# Interfaces_and_Connectors.net
KiCad netlist of a schematic drawn in Altium Designer
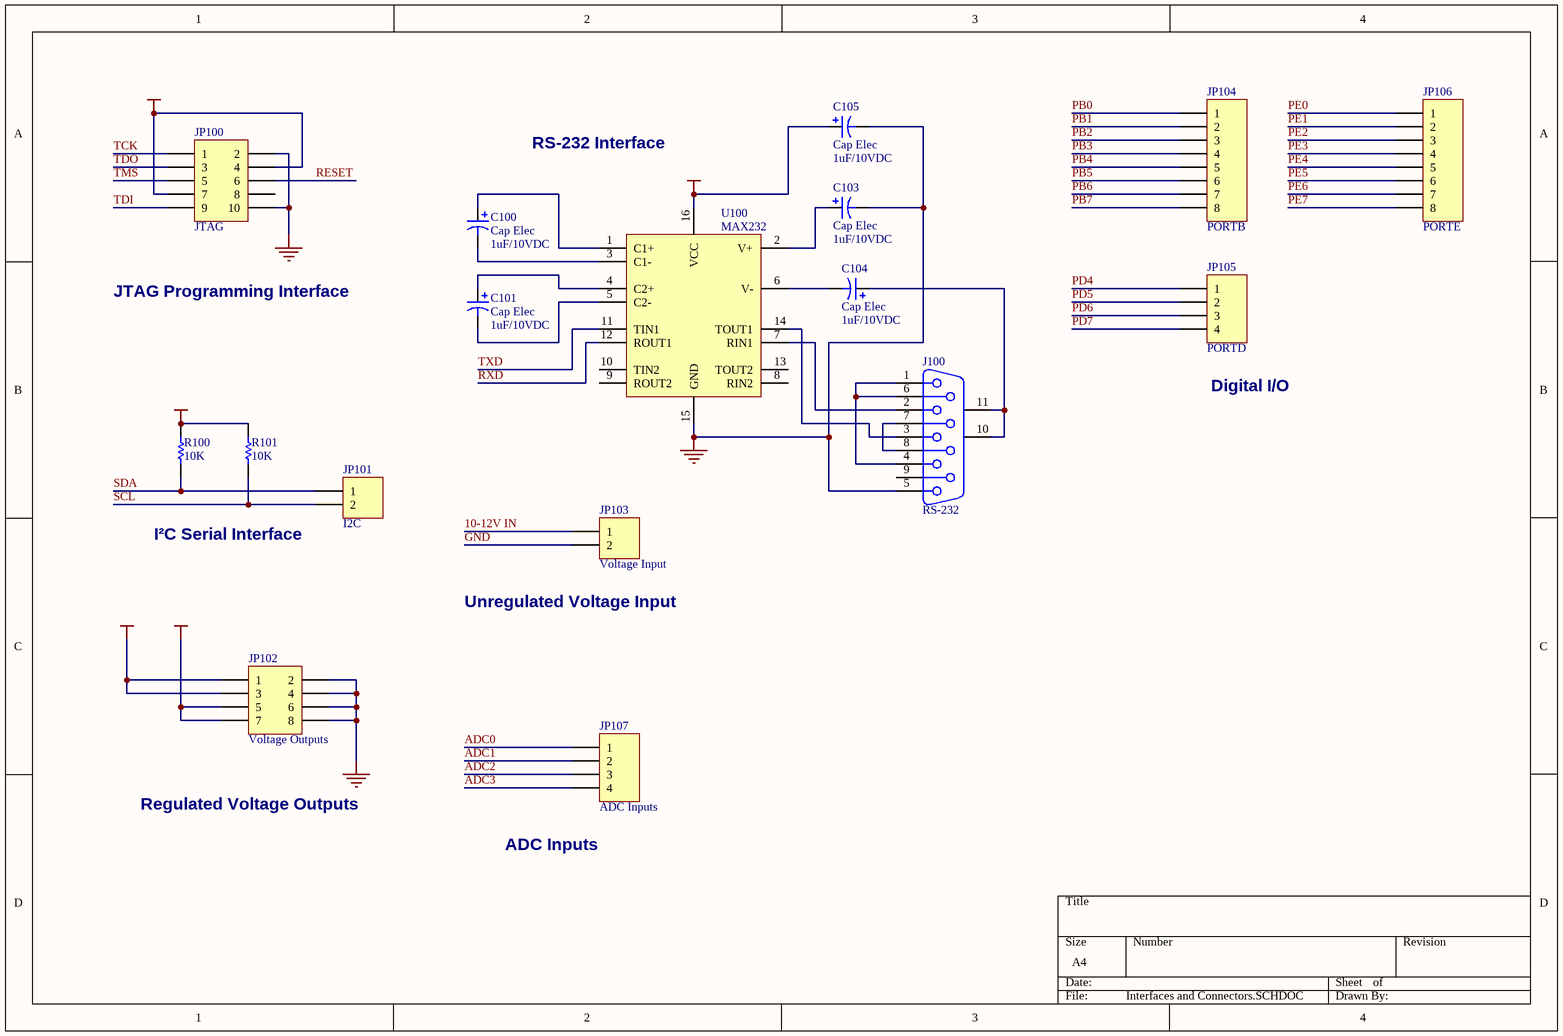
[diagram p0: Interfaces and Connectors.SCHDOC]

(export (version "E")
  (design (tool "Eeschema 10.0.6"))
  (components
    (comp (ref "C100")
      (value "Cap Elec")
      (footprint "CAPR5-4X5")
      (description "Polarized Capacitor (Axial)")
      (fields (field (name "ALTIUM_VALUE") "1uF/10VDC") (field (name "PUBLISHER") "Altium Limited"))
      (libsource (lib "Miscellaneous Devices") (part "Cap Pol2"))
    )
    (comp (ref "C101")
      (value "Cap Elec")
      (footprint "CAPR5-4X5")
      (description "Polarized Capacitor (Axial)")
      (fields (field (name "ALTIUM_VALUE") "1uF/10VDC") (field (name "PUBLISHER") "Altium Limited"))
      (libsource (lib "Miscellaneous Devices") (part "Cap Pol2"))
    )
    (comp (ref "C103")
      (value "Cap Elec")
      (footprint "CAPR5-4X5")
      (description "Polarized Capacitor (Axial)")
      (fields (field (name "ALTIUM_VALUE") "1uF/10VDC") (field (name "PUBLISHER") "Altium Limited"))
      (libsource (lib "Miscellaneous Devices") (part "Cap Pol2"))
    )
    (comp (ref "C104")
      (value "Cap Elec")
      (footprint "CAPR5-4X5")
      (description "Polarized Capacitor (Axial)")
      (fields (field (name "ALTIUM_VALUE") "1uF/10VDC") (field (name "PUBLISHER") "Altium Limited"))
      (libsource (lib "Miscellaneous Devices") (part "Cap Pol2"))
    )
    (comp (ref "C105")
      (value "Cap Elec")
      (footprint "CAPR5-4X5")
      (description "Polarized Capacitor (Axial)")
      (fields (field (name "ALTIUM_VALUE") "1uF/10VDC") (field (name "PUBLISHER") "Altium Limited"))
      (libsource (lib "Miscellaneous Devices") (part "Cap Pol2"))
    )
    (comp (ref "J100")
      (value "RS-232")
      (footprint "DSUB1.385-2H9")
      (description "Receptacle Assembly, 9 Position, Right Angle")
      (fields (field (name "PUBLISHER") "Altium Limited"))
      (libsource (lib "Miscellaneous Connectors") (part "D Connector 9"))
    )
    (comp (ref "JP100")
      (value "JTAG")
      (footprint "HDR2X5")
      (description "Header, 5-Pin, Dual row")
      (fields (field (name "PUBLISHER") "Altium Limited"))
      (libsource (lib "Miscellaneous Connectors") (part "Header 5X2"))
    )
    (comp (ref "JP101")
      (value "I2C")
      (footprint "HDR1X2")
      (description "Header, 2-Pin")
      (fields (field (name "PUBLISHER") "Altium Limited"))
      (libsource (lib "Miscellaneous Connectors") (part "Header 2"))
    )
    (comp (ref "JP102")
      (value "Voltage Outputs")
      (footprint "HDR2X4")
      (description "Header, 4-Pin, Dual row")
      (fields (field (name "PUBLISHER") "Altium Limited"))
      (libsource (lib "Miscellaneous Connectors") (part "Header 4X2"))
    )
    (comp (ref "JP103")
      (value "Voltage Input")
      (footprint "HDR1X2")
      (description "Header, 2-Pin")
      (fields (field (name "PUBLISHER") "Altium Limited"))
      (libsource (lib "Miscellaneous Connectors") (part "Header 2"))
    )
    (comp (ref "JP104")
      (value "PORTB")
      (footprint "HDR1X8")
      (description "Header, 8-Pin")
      (fields (field (name "PUBLISHER") "Altium Limited"))
      (libsource (lib "Miscellaneous Connectors") (part "Header 8"))
    )
    (comp (ref "JP105")
      (value "PORTD")
      (footprint "HDR1X4")
      (description "Header, 4-Pin")
      (fields (field (name "PUBLISHER") "Altium Limited"))
      (libsource (lib "Miscellaneous Connectors") (part "Header 4"))
    )
    (comp (ref "JP106")
      (value "PORTE")
      (footprint "HDR1X8")
      (description "Header, 8-Pin")
      (fields (field (name "PUBLISHER") "Altium Limited"))
      (libsource (lib "Miscellaneous Connectors") (part "Header 8"))
    )
    (comp (ref "JP107")
      (value "ADC Inputs")
      (footprint "HDR1X4")
      (description "Header, 4-Pin")
      (fields (field (name "PUBLISHER") "Altium Limited"))
      (libsource (lib "Miscellaneous Connectors") (part "Header 4"))
    )
    (comp (ref "R100")
      (value "10K")
      (footprint "AXIAL-0.3")
      (description "Resistor")
      (fields (field (name "PUBLISHER") "Altium Limited"))
      (libsource (lib "Miscellaneous Devices") (part "Res1"))
    )
    (comp (ref "R101")
      (value "10K")
      (footprint "AXIAL-0.3")
      (description "Resistor")
      (fields (field (name "PUBLISHER") "Altium Limited"))
      (libsource (lib "Miscellaneous Devices") (part "Res1"))
    )
    (comp (ref "U100")
      (value "MAX232")
      (footprint "SO-G16/C5.85")
      (description "Maxim RS-232 Transceiver")
      (libsource (lib "Schematic Library") (part "MAX232"))
    )
  )
  (nets
    (net (code "1") (name "/10-12V IN") (class "Default")
      (node (ref "JP103") (pin "1") (pinfunction "1_1") (pintype "passive"))
    )
    (net (code "2") (name "/ADC0") (class "Default")
      (node (ref "JP107") (pin "1") (pinfunction "1_1") (pintype "passive"))
    )
    (net (code "3") (name "/ADC1") (class "Default")
      (node (ref "JP107") (pin "2") (pinfunction "2_2") (pintype "passive"))
    )
    (net (code "4") (name "/ADC2") (class "Default")
      (node (ref "JP107") (pin "3") (pinfunction "3_3") (pintype "passive"))
    )
    (net (code "5") (name "/ADC3") (class "Default")
      (node (ref "JP107") (pin "4") (pinfunction "4_4") (pintype "passive"))
    )
    (net (code "6") (name "/PB0") (class "Default")
      (node (ref "JP104") (pin "1") (pinfunction "1_1") (pintype "passive"))
    )
    (net (code "7") (name "/PB1") (class "Default")
      (node (ref "JP104") (pin "2") (pinfunction "2_2") (pintype "passive"))
    )
    (net (code "8") (name "/PB2") (class "Default")
      (node (ref "JP104") (pin "3") (pinfunction "3_3") (pintype "passive"))
    )
    (net (code "9") (name "/PB3") (class "Default")
      (node (ref "JP104") (pin "4") (pinfunction "4_4") (pintype "passive"))
    )
    (net (code "10") (name "/PB4") (class "Default")
      (node (ref "JP104") (pin "5") (pinfunction "5_5") (pintype "passive"))
    )
    (net (code "11") (name "/PB5") (class "Default")
      (node (ref "JP104") (pin "6") (pinfunction "6_6") (pintype "passive"))
    )
    (net (code "12") (name "/PB6") (class "Default")
      (node (ref "JP104") (pin "7") (pinfunction "7_7") (pintype "passive"))
    )
    (net (code "13") (name "/PB7") (class "Default")
      (node (ref "JP104") (pin "8") (pinfunction "8_8") (pintype "passive"))
    )
    (net (code "14") (name "/PD4") (class "Default")
      (node (ref "JP105") (pin "1") (pinfunction "1_1") (pintype "passive"))
    )
    (net (code "15") (name "/PD5") (class "Default")
      (node (ref "JP105") (pin "2") (pinfunction "2_2") (pintype "passive"))
    )
    (net (code "16") (name "/PD6") (class "Default")
      (node (ref "JP105") (pin "3") (pinfunction "3_3") (pintype "passive"))
    )
    (net (code "17") (name "/PD7") (class "Default")
      (node (ref "JP105") (pin "4") (pinfunction "4_4") (pintype "passive"))
    )
    (net (code "18") (name "/PE0") (class "Default")
      (node (ref "JP106") (pin "1") (pinfunction "1_1") (pintype "passive"))
    )
    (net (code "19") (name "/PE1") (class "Default")
      (node (ref "JP106") (pin "2") (pinfunction "2_2") (pintype "passive"))
    )
    (net (code "20") (name "/PE2") (class "Default")
      (node (ref "JP106") (pin "3") (pinfunction "3_3") (pintype "passive"))
    )
    (net (code "21") (name "/PE3") (class "Default")
      (node (ref "JP106") (pin "4") (pinfunction "4_4") (pintype "passive"))
    )
    (net (code "22") (name "/PE4") (class "Default")
      (node (ref "JP106") (pin "5") (pinfunction "5_5") (pintype "passive"))
    )
    (net (code "23") (name "/PE5") (class "Default")
      (node (ref "JP106") (pin "6") (pinfunction "6_6") (pintype "passive"))
    )
    (net (code "24") (name "/PE6") (class "Default")
      (node (ref "JP106") (pin "7") (pinfunction "7_7") (pintype "passive"))
    )
    (net (code "25") (name "/PE7") (class "Default")
      (node (ref "JP106") (pin "8") (pinfunction "8_8") (pintype "passive"))
    )
    (net (code "26") (name "/RESET") (class "Default")
      (node (ref "JP100") (pin "6") (pinfunction "6_6") (pintype "passive"))
    )
    (net (code "27") (name "/RXD") (class "Default")
      (node (ref "U100") (pin "12") (pinfunction "ROUT1_12") (pintype "passive"))
    )
    (net (code "28") (name "/SCL") (class "Default")
      (node (ref "JP101") (pin "2") (pinfunction "2_2") (pintype "passive"))
      (node (ref "R101") (pin "1") (pinfunction "1_1") (pintype "passive"))
    )
    (net (code "29") (name "/SDA") (class "Default")
      (node (ref "JP101") (pin "1") (pinfunction "1_1") (pintype "passive"))
      (node (ref "R100") (pin "1") (pinfunction "1_1") (pintype "passive"))
    )
    (net (code "30") (name "/TCK") (class "Default")
      (node (ref "JP100") (pin "1") (pinfunction "1_1") (pintype "passive"))
    )
    (net (code "31") (name "/TDI") (class "Default")
      (node (ref "JP100") (pin "9") (pinfunction "9_9") (pintype "passive"))
    )
    (net (code "32") (name "/TDO") (class "Default")
      (node (ref "JP100") (pin "3") (pinfunction "3_3") (pintype "passive"))
    )
    (net (code "33") (name "/TMS") (class "Default")
      (node (ref "JP100") (pin "5") (pinfunction "5_5") (pintype "passive"))
    )
    (net (code "34") (name "/TXD") (class "Default")
      (node (ref "U100") (pin "11") (pinfunction "TIN1_11") (pintype "passive"))
    )
    (net (code "35") (name "5V") (class "Default")
      (node (ref "C105") (pin "1") (pinfunction "1_1") (pintype "passive"))
      (node (ref "JP100") (pin "4") (pinfunction "4_4") (pintype "passive"))
      (node (ref "JP100") (pin "7") (pinfunction "7_7") (pintype "passive"))
      (node (ref "JP102") (pin "5") (pinfunction "5_5") (pintype "passive"))
      (node (ref "JP102") (pin "7") (pinfunction "7_7") (pintype "passive"))
      (node (ref "R100") (pin "2") (pinfunction "2_2") (pintype "passive"))
      (node (ref "R101") (pin "2") (pinfunction "2_2") (pintype "passive"))
      (node (ref "U100") (pin "16") (pinfunction "VCC_16") (pintype "passive"))
    )
    (net (code "36") (name "9V") (class "Default")
      (node (ref "JP102") (pin "1") (pinfunction "1_1") (pintype "passive"))
      (node (ref "JP102") (pin "3") (pinfunction "3_3") (pintype "passive"))
    )
    (net (code "37") (name "GND") (class "Default")
      (node (ref "C103") (pin "2") (pinfunction "2_2") (pintype "passive"))
      (node (ref "C105") (pin "2") (pinfunction "2_2") (pintype "passive"))
      (node (ref "J100") (pin "5") (pinfunction "5_5") (pintype "passive"))
      (node (ref "JP100") (pin "10") (pinfunction "10_10") (pintype "passive"))
      (node (ref "JP100") (pin "2") (pinfunction "2_2") (pintype "passive"))
      (node (ref "JP102") (pin "2") (pinfunction "2_2") (pintype "passive"))
      (node (ref "JP102") (pin "4") (pinfunction "4_4") (pintype "passive"))
      (node (ref "JP102") (pin "6") (pinfunction "6_6") (pintype "passive"))
      (node (ref "JP102") (pin "8") (pinfunction "8_8") (pintype "passive"))
      (node (ref "JP103") (pin "2") (pinfunction "2_2") (pintype "passive"))
      (node (ref "U100") (pin "15") (pinfunction "GND_15") (pintype "passive"))
    )
    (net (code "38") (name "Net-(J100-MH1)") (class "Default")
      (node (ref "C104") (pin "1") (pinfunction "1_1") (pintype "passive"))
      (node (ref "J100") (pin "10") (pinfunction "MH1_10") (pintype "passive"))
      (node (ref "J100") (pin "11") (pinfunction "MH2_11") (pintype "passive"))
    )
    (net (code "39") (name "Net-(J100-Pad1)") (class "Default")
      (node (ref "J100") (pin "1") (pinfunction "1_1") (pintype "passive"))
      (node (ref "J100") (pin "4") (pinfunction "4_4") (pintype "passive"))
      (node (ref "J100") (pin "6") (pinfunction "6_6") (pintype "passive"))
    )
    (net (code "40") (name "Net-(J100-Pad7)") (class "Default")
      (node (ref "J100") (pin "7") (pinfunction "7_7") (pintype "passive"))
      (node (ref "J100") (pin "8") (pinfunction "8_8") (pintype "passive"))
    )
    (net (code "41") (name "Net-(U100-C1+)") (class "Default")
      (node (ref "C100") (pin "1") (pinfunction "1_1") (pintype "passive"))
      (node (ref "U100") (pin "1") (pinfunction "C1+_1") (pintype "passive"))
    )
    (net (code "42") (name "Net-(U100-C1-)") (class "Default")
      (node (ref "C100") (pin "2") (pinfunction "2_2") (pintype "passive"))
      (node (ref "U100") (pin "3") (pinfunction "C1-_3") (pintype "passive"))
    )
    (net (code "43") (name "Net-(U100-C2+)") (class "Default")
      (node (ref "C101") (pin "1") (pinfunction "1_1") (pintype "passive"))
      (node (ref "U100") (pin "4") (pinfunction "C2+_4") (pintype "passive"))
    )
    (net (code "44") (name "Net-(U100-C2-)") (class "Default")
      (node (ref "C101") (pin "2") (pinfunction "2_2") (pintype "passive"))
      (node (ref "U100") (pin "5") (pinfunction "C2-_5") (pintype "passive"))
    )
    (net (code "45") (name "Net-(U100-RIN1)") (class "Default")
      (node (ref "J100") (pin "2") (pinfunction "2_2") (pintype "passive"))
      (node (ref "U100") (pin "7") (pinfunction "RIN1_7") (pintype "passive"))
    )
    (net (code "46") (name "Net-(U100-TOUT1)") (class "Default")
      (node (ref "J100") (pin "3") (pinfunction "3_3") (pintype "passive"))
      (node (ref "U100") (pin "14") (pinfunction "TOUT1_14") (pintype "passive"))
    )
    (net (code "47") (name "Net-(U100-V+)") (class "Default")
      (node (ref "C103") (pin "1") (pinfunction "1_1") (pintype "passive"))
      (node (ref "U100") (pin "2") (pinfunction "V+_2") (pintype "passive"))
    )
    (net (code "48") (name "Net-(U100-V-)") (class "Default")
      (node (ref "C104") (pin "2") (pinfunction "2_2") (pintype "passive"))
      (node (ref "U100") (pin "6") (pinfunction "V-_6") (pintype "passive"))
    )
    (net (code "49") (name "unconnected-(J100-Pad9)") (class "Default")
      (node (ref "J100") (pin "9") (pinfunction "9_9") (pintype "passive"))
    )
    (net (code "50") (name "unconnected-(JP100-Pad8)") (class "Default")
      (node (ref "JP100") (pin "8") (pinfunction "8_8") (pintype "passive"))
    )
    (net (code "51") (name "unconnected-(U100-RIN2-Pad8)") (class "Default")
      (node (ref "U100") (pin "8") (pinfunction "RIN2_8") (pintype "passive"))
    )
    (net (code "52") (name "unconnected-(U100-ROUT2-Pad9)") (class "Default")
      (node (ref "U100") (pin "9") (pinfunction "ROUT2_9") (pintype "passive"))
    )
    (net (code "53") (name "unconnected-(U100-TIN2-Pad10)") (class "Default")
      (node (ref "U100") (pin "10") (pinfunction "TIN2_10") (pintype "passive"))
    )
    (net (code "54") (name "unconnected-(U100-TOUT2-Pad13)") (class "Default")
      (node (ref "U100") (pin "13") (pinfunction "TOUT2_13") (pintype "passive"))
    )
  )
)
